# BatteryCharging.net
KiCad netlist of a schematic drawn in EAGLE
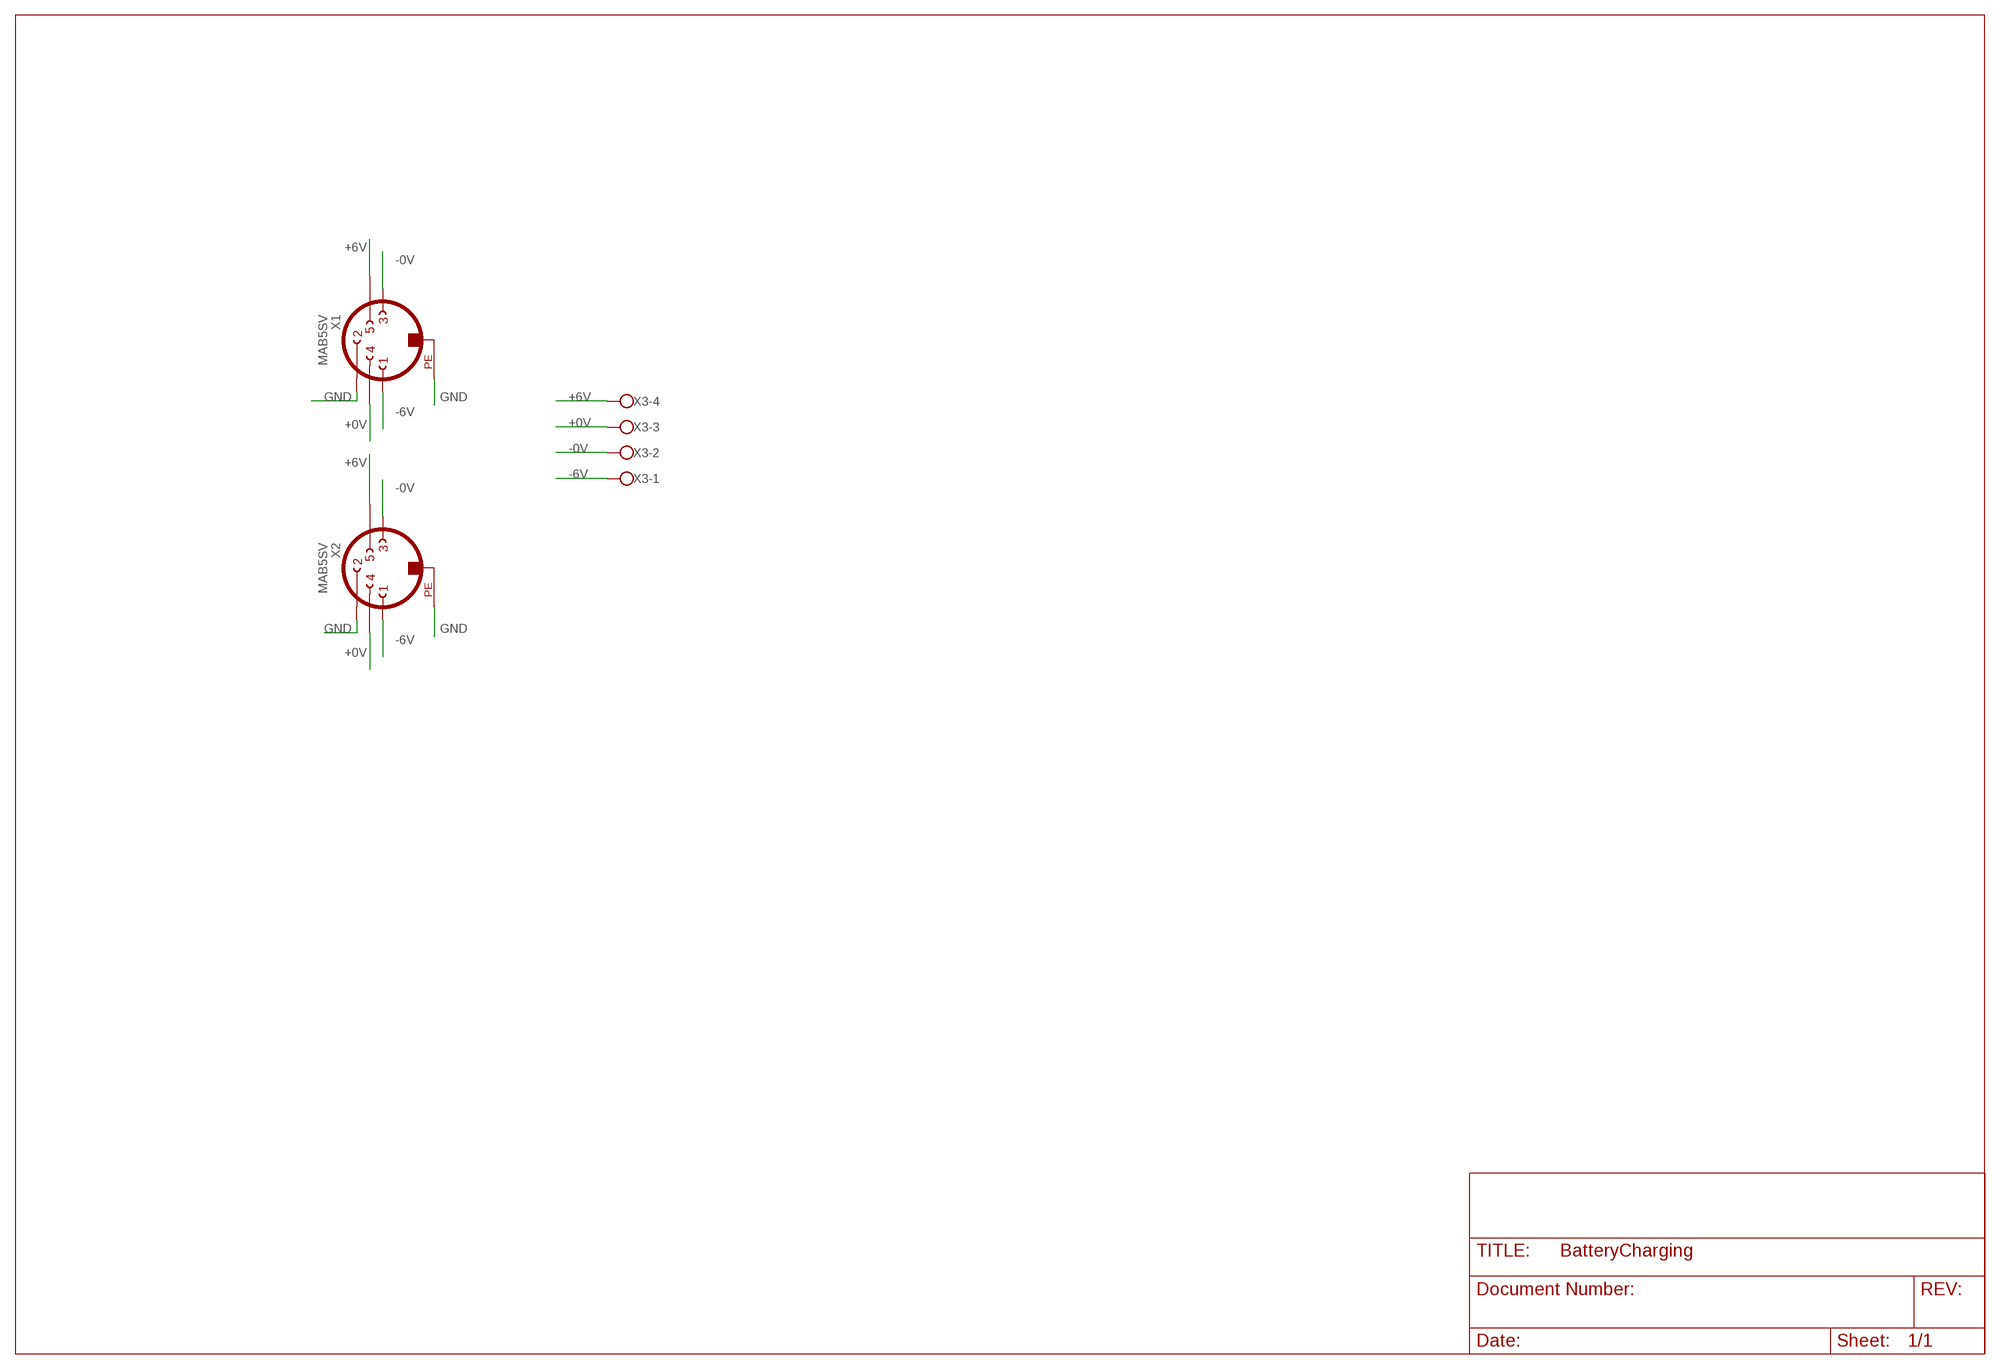
[diagram p0: schematic, sheet 1]

(export (version "E")
  (design (tool "Eeschema 10.0.6"))
  (components
    (comp (ref "X1")
      (value "MAB5SV")
      (footprint "eagle-import:MAB5SV")
      (libsource (lib "eagle-import") (part "MAB5SV"))
    )
    (comp (ref "X2")
      (value "MAB5SV")
      (footprint "eagle-import:MAB5SV")
      (libsource (lib "eagle-import") (part "MAB5SV"))
    )
    (comp (ref "X3")
      (value "W237-4")
      (footprint "eagle-import:W237-4")
      (libsource (lib "eagle-import") (part "W237-4"))
    )
  )
  (nets
    (net (code "1") (name "/+0V") (class "Default")
      (node (ref "X1") (pin "4") (pinfunction "4_4") (pintype "passive"))
      (node (ref "X2") (pin "4") (pinfunction "4_4") (pintype "passive"))
      (node (ref "X3") (pin "3") (pinfunction "KL_3") (pintype "passive"))
    )
    (net (code "2") (name "/+6V") (class "Default")
      (node (ref "X1") (pin "5") (pinfunction "5_5") (pintype "passive"))
      (node (ref "X2") (pin "5") (pinfunction "5_5") (pintype "passive"))
      (node (ref "X3") (pin "4") (pinfunction "KL_4") (pintype "passive"))
    )
    (net (code "3") (name "/-0V") (class "Default")
      (node (ref "X1") (pin "3") (pinfunction "3_3") (pintype "passive"))
      (node (ref "X2") (pin "3") (pinfunction "3_3") (pintype "passive"))
      (node (ref "X3") (pin "2") (pinfunction "KL_2") (pintype "passive"))
    )
    (net (code "4") (name "/-6V") (class "Default")
      (node (ref "X1") (pin "1") (pinfunction "1_1") (pintype "passive"))
      (node (ref "X2") (pin "1") (pinfunction "1_1") (pintype "passive"))
      (node (ref "X3") (pin "1") (pinfunction "KL_1") (pintype "passive"))
    )
    (net (code "5") (name "/GND") (class "Default")
      (node (ref "X1") (pin "2") (pinfunction "2_2") (pintype "passive"))
      (node (ref "X1") (pin "PE") (pinfunction "PE_PE") (pintype "power_in"))
      (node (ref "X2") (pin "2") (pinfunction "2_2") (pintype "passive"))
      (node (ref "X2") (pin "PE") (pinfunction "PE_PE") (pintype "power_in"))
    )
  )
)
